# SW108_0713.net
KiCad netlist of a schematic drawn in Altium Designer
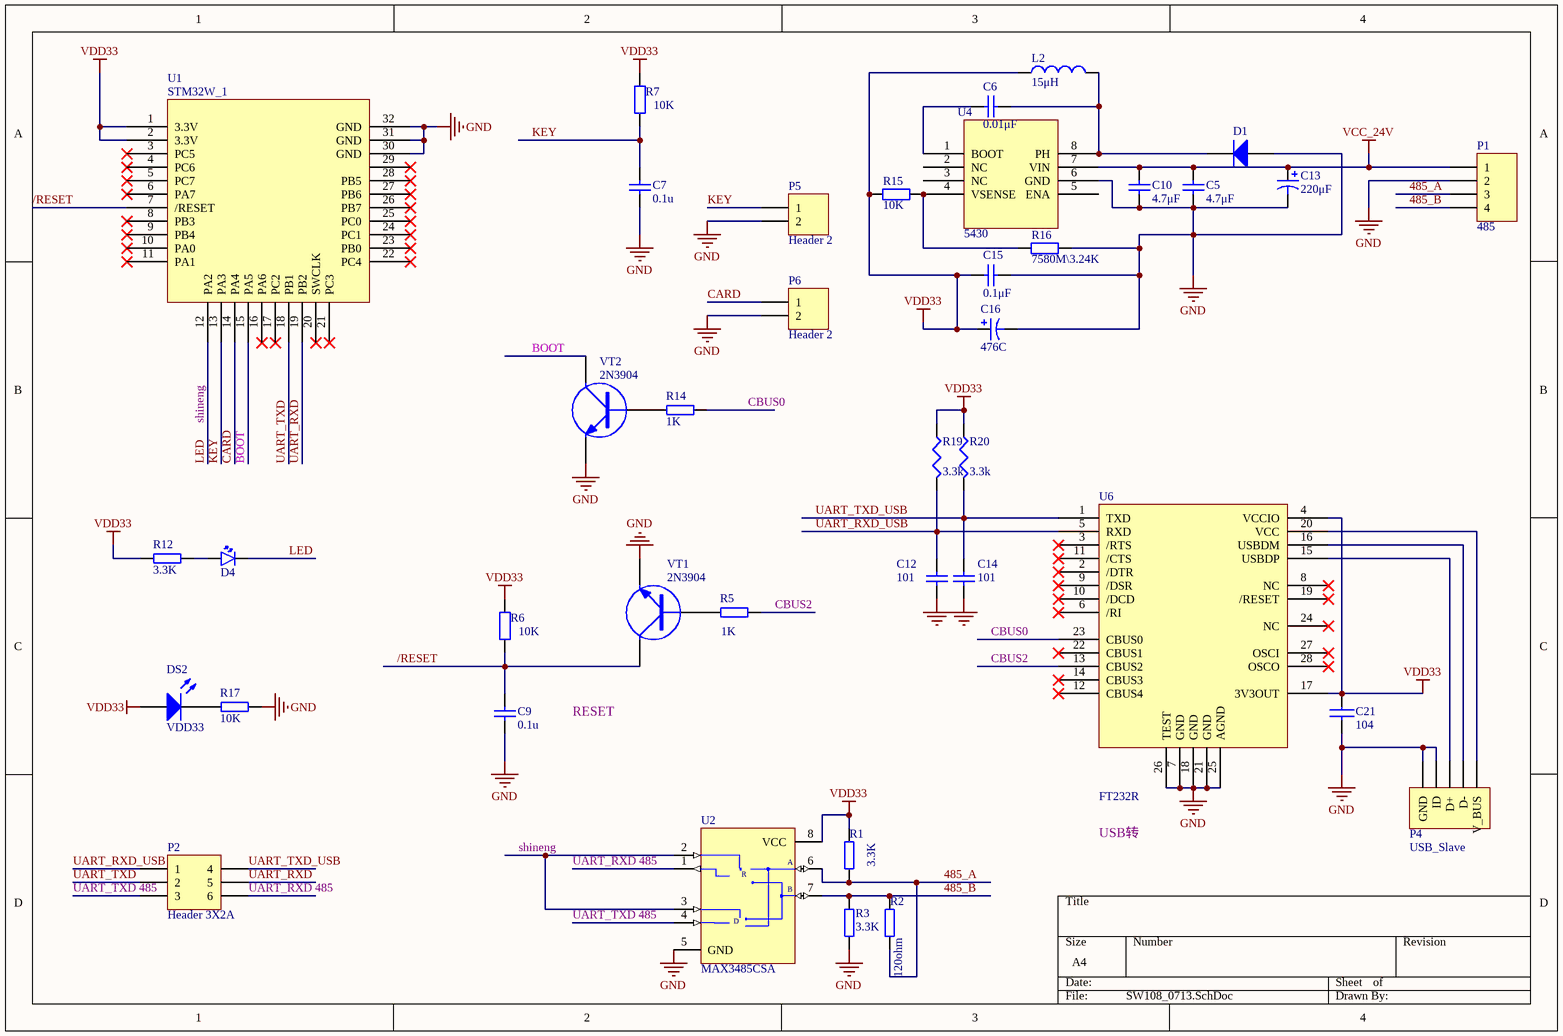
[diagram p0: SW108_0713.SchDoc]

(export (version "E")
  (design (tool "Eeschema 10.0.6"))
  (components
    (comp (ref "C5")
      (value "4.7μF")
      (footprint "C0603")
      (description "Capacitor")
      (fields (field (name "PUBLISHER") "Altium Limited"))
      (libsource (lib "Miscellaneous Devices") (part "Cap"))
    )
    (comp (ref "C6")
      (value "0.01μF")
      (footprint "C0603")
      (description "Capacitor")
      (fields (field (name "PUBLISHER") "Altium Limited"))
      (libsource (lib "Miscellaneous Devices") (part "Cap"))
    )
    (comp (ref "C7")
      (value "0.1u")
      (footprint "C0603")
      (description "Capacitor")
      (fields (field (name "PUBLISHER") "Altium Limited"))
      (libsource (lib "Miscellaneous Devices") (part "Cap"))
    )
    (comp (ref "C9")
      (value "0.1u")
      (footprint "C0603")
      (description "Capacitor")
      (fields (field (name "PUBLISHER") "Altium Limited"))
      (libsource (lib "Miscellaneous Devices") (part "Cap"))
    )
    (comp (ref "C10")
      (value "4.7μF")
      (footprint "C0603")
      (description "Capacitor")
      (fields (field (name "PUBLISHER") "Altium Limited"))
      (libsource (lib "Miscellaneous Devices") (part "Cap"))
    )
    (comp (ref "C12")
      (value "101")
      (footprint "C0603")
      (description "Capacitor")
      (fields (field (name "PUBLISHER") "Altium Limited"))
      (libsource (lib "Miscellaneous Devices") (part "Cap"))
    )
    (comp (ref "C13")
      (value "220μF")
      (footprint "CZ3.0/6.5")
      (description "Polarized Capacitor (Radial)")
      (fields (field (name "PUBLISHER") "Altium Limited"))
      (libsource (lib "Miscellaneous Devices") (part "Cap Pol1"))
    )
    (comp (ref "C14")
      (value "101")
      (footprint "C0603")
      (description "Capacitor")
      (fields (field (name "PUBLISHER") "Altium Limited"))
      (libsource (lib "Miscellaneous Devices") (part "Cap"))
    )
    (comp (ref "C15")
      (value "0.1μF")
      (footprint "C0603")
      (description "Capacitor")
      (fields (field (name "PUBLISHER") "Altium Limited"))
      (libsource (lib "Miscellaneous Devices") (part "Cap"))
    )
    (comp (ref "C16")
      (value "476C")
      (footprint "7343")
      (description "Polarized Capacitor (Radial)")
      (fields (field (name "PUBLISHER") "Altium Limited"))
      (libsource (lib "Miscellaneous Devices") (part "Cap Pol1"))
    )
    (comp (ref "C21") (value "104") (footprint "C0603") (description "C") (libsource (lib "Haze") (part "C")))
    (comp (ref "D1")
      (value "Diode 1N5408")
      (footprint "UF3B")
      (description "3 Amp Medium Power Silicon Rectifier Diode")
      (fields (field (name "PUBLISHER") "Altium Limited"))
      (libsource (lib "Miscellaneous Devices") (part "Diode 1N5408"))
    )
    (comp (ref "D4") (value "green LED") (footprint "LED") (libsource (lib "Haze") (part "LED")))
    (comp (ref "DS2")
      (value "VDD33")
      (footprint "LED")
      (description "Typical BLUE SiC LED")
      (fields (field (name "PUBLISHER") "Altium Limited"))
      (libsource (lib "Miscellaneous Devices") (part "LED3"))
    )
    (comp (ref "L2")
      (value "15μH")
      (footprint "L2")
      (description "Inductor")
      (fields (field (name "PUBLISHER") "Altium Limited"))
      (libsource (lib "Miscellaneous Devices") (part "Inductor"))
    )
    (comp (ref "P1")
      (value "485")
      (footprint "4kongzhen")
      (description "Header, 4-Pin")
      (fields (field (name "PUBLISHER") "Altium Limited"))
      (libsource (lib "Miscellaneous Connectors") (part "Header 4"))
    )
    (comp (ref "P2")
      (value "Header 3X2A")
      (footprint "HDR2X3_CEN")
      (description "Header, 3-Pin, Dual row")
      (fields (field (name "PUBLISHER") "Altium Limited"))
      (libsource (lib "Miscellaneous Connectors") (part "Header 3X2A"))
    )
    (comp (ref "P4")
      (value "USB_Slave")
      (footprint "USBfoot")
      (description "Header, 5-Pin")
      (fields (field (name "PUBLISHER") "Altium Limited"))
      (libsource (lib "Miscellaneous Connectors") (part "Header 5"))
    )
    (comp (ref "P5")
      (value "Header 2")
      (footprint "HDR1X2")
      (description "Header, 2-Pin")
      (fields (field (name "PUBLISHER") "Altium Limited"))
      (libsource (lib "Miscellaneous Connectors") (part "Header 2"))
    )
    (comp (ref "P6")
      (value "Header 2")
      (footprint "HDR1X2")
      (description "Header, 2-Pin")
      (fields (field (name "PUBLISHER") "Altium Limited"))
      (libsource (lib "Miscellaneous Connectors") (part "Header 2"))
    )
    (comp (ref "R1")
      (value "3.3K")
      (footprint "R0603")
      (description "R")
      (libsource (lib "Haze") (part "RES"))
    )
    (comp (ref "R2")
      (value "120ohm")
      (footprint "R0603")
      (description "R")
      (libsource (lib "Haze") (part "RES"))
    )
    (comp (ref "R3")
      (value "3.3K")
      (footprint "R0603")
      (description "R")
      (libsource (lib "Haze") (part "RES"))
    )
    (comp (ref "R5") (value "1K") (footprint "R0603") (description "R") (libsource (lib "Haze") (part "RES")))
    (comp (ref "R6")
      (value "10K")
      (footprint "R0603")
      (description "Resistor")
      (fields (field (name "Comment") "Res2") (field (name "PUBLISHER") "Altium Limited"))
      (libsource (lib "") (part "Res2_1"))
    )
    (comp (ref "R7")
      (value "10K")
      (footprint "R0603")
      (description "Resistor")
      (fields (field (name "Comment") "Res2") (field (name "PUBLISHER") "Altium Limited"))
      (libsource (lib "") (part "Res2_1"))
    )
    (comp (ref "R12")
      (value "3.3K")
      (footprint "R0603")
      (description "R")
      (libsource (lib "Haze") (part "RES"))
    )
    (comp (ref "R14")
      (value "1K")
      (footprint "R0603")
      (description "R")
      (libsource (lib "Haze") (part "RES"))
    )
    (comp (ref "R15")
      (value "10K")
      (footprint "R0603")
      (description "Resistor")
      (fields (field (name "PUBLISHER") "Altium Limited"))
      (libsource (lib "Miscellaneous Devices") (part "Res2"))
    )
    (comp (ref "R16")
      (value "7580~{M}3.24K")
      (footprint "R0603")
      (description "Resistor")
      (fields (field (name "PUBLISHER") "Altium Limited"))
      (libsource (lib "Miscellaneous Devices") (part "Res2"))
    )
    (comp (ref "R17")
      (value "10K")
      (footprint "R0603")
      (description "R")
      (libsource (lib "Haze") (part "RES"))
    )
    (comp (ref "R19")
      (value "3.3k")
      (footprint "R0603")
      (description "Resistor")
      (fields (field (name "PUBLISHER") "Altium Limited"))
      (libsource (lib "Miscellaneous Devices") (part "Res3"))
    )
    (comp (ref "R20")
      (value "3.3k")
      (footprint "R0603")
      (description "Resistor")
      (fields (field (name "PUBLISHER") "Altium Limited"))
      (libsource (lib "Miscellaneous Devices") (part "Res3"))
    )
    (comp (ref "U1")
      (value "STM32W_1")
      (footprint "STM32W108-3")
      (libsource (lib "STM32W108-3") (part "STM32W108-3"))
    )
    (comp (ref "U2")
      (value "MAX3485CSA")
      (footprint "SO-8")
      (description "Low-Power, Slew-Rate-Limited RS-485/RS-422 Transceiver")
      (fields (field (name "PUBLISHER") "Altium Limited"))
      (libsource (lib "Maxim Communication Transceiver") (part "MAX485CSA"))
    )
    (comp (ref "U4") (value "5430") (footprint "SO-8") (libsource (lib "Haze") (part "5430")))
    (comp (ref "U6") (value "FT232R") (footprint "SSOP-28") (libsource (lib "Haze") (part "FT232R")))
    (comp (ref "VT1")
      (value "2N3904")
      (footprint "SOT23-3")
      (description "NPN Transistor")
      (libsource (lib "Haze") (part "NPN"))
    )
    (comp (ref "VT2")
      (value "2N3904")
      (footprint "SOT23-3")
      (description "NPN Transistor")
      (libsource (lib "Haze") (part "NPN"))
    )
  )
  (nets
    (net (code "1") (name "/485_A") (class "Default")
      (node (ref "P1") (pin "3") (pinfunction "3_3") (pintype "passive"))
      (node (ref "R1") (pin "1") (pinfunction "1_1") (pintype "passive"))
      (node (ref "R2") (pin "2") (pinfunction "2_2") (pintype "passive"))
      (node (ref "U2") (pin "6") (pinfunction "A_6") (pintype "bidirectional"))
    )
    (net (code "2") (name "/485_B") (class "Default")
      (node (ref "P1") (pin "4") (pinfunction "4_4") (pintype "passive"))
      (node (ref "R2") (pin "1") (pinfunction "1_1") (pintype "passive"))
      (node (ref "R3") (pin "2") (pinfunction "2_2") (pintype "passive"))
      (node (ref "U2") (pin "7") (pinfunction "B_7") (pintype "bidirectional"))
    )
    (net (code "3") (name "/BOOT") (class "Default")
      (node (ref "U1") (pin "15") (pinfunction "PA5_15") (pintype "passive"))
      (node (ref "VT2") (pin "3") (pinfunction "C_3") (pintype "passive"))
    )
    (net (code "4") (name "/CARD") (class "Default")
      (node (ref "P6") (pin "1") (pinfunction "1_1") (pintype "passive"))
      (node (ref "U1") (pin "14") (pinfunction "PA4_14") (pintype "passive"))
    )
    (net (code "5") (name "/CBUS0") (class "Default")
      (node (ref "R14") (pin "2") (pinfunction "2_2") (pintype "passive"))
      (node (ref "U6") (pin "23") (pinfunction "CBUS0_23") (pintype "passive"))
    )
    (net (code "6") (name "/CBUS2") (class "Default")
      (node (ref "R5") (pin "2") (pinfunction "2_2") (pintype "passive"))
      (node (ref "U6") (pin "13") (pinfunction "CBUS2_13") (pintype "passive"))
    )
    (net (code "7") (name "/KEY") (class "Default")
      (node (ref "C7") (pin "2") (pinfunction "2_2") (pintype "passive"))
      (node (ref "P5") (pin "1") (pinfunction "1_1") (pintype "passive"))
      (node (ref "R7") (pin "1") (pinfunction "1_1") (pintype "passive"))
      (node (ref "U1") (pin "13") (pinfunction "PA3_13") (pintype "passive"))
    )
    (net (code "8") (name "/LED") (class "Default")
      (node (ref "D4") (pin "2") (pinfunction "K_2") (pintype "passive"))
      (node (ref "U1") (pin "12") (pinfunction "PA2_12") (pintype "passive"))
      (node (ref "U2") (pin "2") (pinfunction "~{RE}_2") (pintype "input"))
      (node (ref "U2") (pin "3") (pinfunction "DE_3") (pintype "input"))
    )
    (net (code "9") (name "/UART_RXD") (class "Default")
      (node (ref "P2") (pin "5") (pinfunction "5_5") (pintype "passive"))
      (node (ref "U1") (pin "19") (pinfunction "PB2_19") (pintype "passive"))
    )
    (net (code "10") (name "/UART_RXD 485") (class "Default")
      (node (ref "P2") (pin "6") (pinfunction "6_6") (pintype "passive"))
      (node (ref "U2") (pin "1") (pinfunction "RO_1") (pintype "output"))
    )
    (net (code "11") (name "/UART_RXD_USB") (class "Default")
      (node (ref "C12") (pin "2") (pinfunction "2_2") (pintype "passive"))
      (node (ref "P2") (pin "1") (pinfunction "1_1") (pintype "passive"))
      (node (ref "R19") (pin "2") (pinfunction "2_2") (pintype "passive"))
      (node (ref "U6") (pin "5") (pinfunction "RXD_5") (pintype "passive"))
    )
    (net (code "12") (name "/UART_TXD") (class "Default")
      (node (ref "P2") (pin "2") (pinfunction "2_2") (pintype "passive"))
      (node (ref "U1") (pin "18") (pinfunction "PB1_18") (pintype "passive"))
    )
    (net (code "13") (name "/UART_TXD 485") (class "Default")
      (node (ref "P2") (pin "3") (pinfunction "3_3") (pintype "passive"))
      (node (ref "U2") (pin "4") (pinfunction "DI_4") (pintype "input"))
    )
    (net (code "14") (name "/UART_TXD_USB") (class "Default")
      (node (ref "C14") (pin "2") (pinfunction "2_2") (pintype "passive"))
      (node (ref "P2") (pin "4") (pinfunction "4_4") (pintype "passive"))
      (node (ref "R20") (pin "2") (pinfunction "2_2") (pintype "passive"))
      (node (ref "U6") (pin "1") (pinfunction "TXD_1") (pintype "passive"))
    )
    (net (code "15") (name "/{slash}RESET") (class "Default")
      (node (ref "C9") (pin "2") (pinfunction "2_2") (pintype "passive"))
      (node (ref "R6") (pin "1") (pinfunction "1_1") (pintype "passive"))
      (node (ref "U1") (pin "7") (pinfunction "/RESET_7") (pintype "passive"))
      (node (ref "VT1") (pin "3") (pinfunction "C_3") (pintype "passive"))
    )
    (net (code "16") (name "GND") (class "Default")
      (node (ref "C10") (pin "1") (pinfunction "1_1") (pintype "passive"))
      (node (ref "C12") (pin "1") (pinfunction "1_1") (pintype "passive"))
      (node (ref "C13") (pin "2") (pinfunction "2_2") (pintype "passive"))
      (node (ref "C14") (pin "1") (pinfunction "1_1") (pintype "passive"))
      (node (ref "C15") (pin "2") (pinfunction "2_2") (pintype "passive"))
      (node (ref "C16") (pin "2") (pinfunction "2_2") (pintype "passive"))
      (node (ref "C21") (pin "2") (pinfunction "2_2") (pintype "passive"))
      (node (ref "C5") (pin "1") (pinfunction "1_1") (pintype "passive"))
      (node (ref "C7") (pin "1") (pinfunction "1_1") (pintype "passive"))
      (node (ref "C9") (pin "1") (pinfunction "1_1") (pintype "passive"))
      (node (ref "D1") (pin "1") (pinfunction "A_1") (pintype "passive"))
      (node (ref "P1") (pin "2") (pinfunction "2_2") (pintype "passive"))
      (node (ref "P4") (pin "4") (pinfunction "ID_4") (pintype "passive"))
      (node (ref "P4") (pin "5") (pinfunction "GND_5") (pintype "passive"))
      (node (ref "P5") (pin "2") (pinfunction "2_2") (pintype "passive"))
      (node (ref "P6") (pin "2") (pinfunction "2_2") (pintype "passive"))
      (node (ref "R16") (pin "2") (pinfunction "2_2") (pintype "passive"))
      (node (ref "R17") (pin "1") (pinfunction "1_1") (pintype "passive"))
      (node (ref "R3") (pin "1") (pinfunction "1_1") (pintype "passive"))
      (node (ref "U1") (pin "30") (pinfunction "GND_30") (pintype "passive"))
      (node (ref "U1") (pin "31") (pinfunction "GND_31") (pintype "passive"))
      (node (ref "U1") (pin "32") (pinfunction "GND_32") (pintype "passive"))
      (node (ref "U2") (pin "5") (pinfunction "GND_5") (pintype "power_in"))
      (node (ref "U4") (pin "6") (pinfunction "GND_6") (pintype "passive"))
      (node (ref "U6") (pin "18") (pinfunction "GND_18") (pintype "passive"))
      (node (ref "U6") (pin "21") (pinfunction "GND_21") (pintype "passive"))
      (node (ref "U6") (pin "25") (pinfunction "AGND_25") (pintype "passive"))
      (node (ref "U6") (pin "26") (pinfunction "TEST_26") (pintype "passive"))
      (node (ref "U6") (pin "7") (pinfunction "GND_7") (pintype "passive"))
      (node (ref "VT1") (pin "2") (pinfunction "E_2") (pintype "passive"))
      (node (ref "VT2") (pin "2") (pinfunction "E_2") (pintype "passive"))
    )
    (net (code "17") (name "Net-(D1-K)") (class "Default")
      (node (ref "C6") (pin "2") (pinfunction "2_2") (pintype "passive"))
      (node (ref "D1") (pin "2") (pinfunction "K_2") (pintype "passive"))
      (node (ref "L2") (pin "2") (pinfunction "2_2") (pintype "passive"))
      (node (ref "U4") (pin "8") (pinfunction "PH_8") (pintype "passive"))
    )
    (net (code "18") (name "Net-(D4-A)") (class "Default")
      (node (ref "D4") (pin "1") (pinfunction "A_1") (pintype "passive"))
      (node (ref "R12") (pin "2") (pinfunction "2_2") (pintype "passive"))
    )
    (net (code "19") (name "Net-(DS2-K)") (class "Default")
      (node (ref "DS2") (pin "2") (pinfunction "K_2") (pintype "passive"))
      (node (ref "R17") (pin "2") (pinfunction "2_2") (pintype "passive"))
    )
    (net (code "20") (name "Net-(P4-D+)") (class "Default")
      (node (ref "P4") (pin "3") (pinfunction "D+_3") (pintype "passive"))
      (node (ref "U6") (pin "15") (pinfunction "USBDP_15") (pintype "passive"))
    )
    (net (code "21") (name "Net-(P4-D-)") (class "Default")
      (node (ref "P4") (pin "2") (pinfunction "D-_2") (pintype "passive"))
      (node (ref "U6") (pin "16") (pinfunction "USBDM_16") (pintype "passive"))
    )
    (net (code "22") (name "Net-(P4-V_BUS)") (class "Default")
      (node (ref "P4") (pin "1") (pinfunction "V_BUS_1") (pintype "passive"))
      (node (ref "U6") (pin "20") (pinfunction "VCC_20") (pintype "passive"))
    )
    (net (code "23") (name "Net-(U4-BOOT)") (class "Default")
      (node (ref "C6") (pin "1") (pinfunction "1_1") (pintype "passive"))
      (node (ref "U4") (pin "1") (pinfunction "BOOT_1") (pintype "passive"))
    )
    (net (code "24") (name "Net-(U4-VSENSE)") (class "Default")
      (node (ref "R15") (pin "2") (pinfunction "2_2") (pintype "passive"))
      (node (ref "R16") (pin "1") (pinfunction "1_1") (pintype "passive"))
      (node (ref "U4") (pin "4") (pinfunction "VSENSE_4") (pintype "passive"))
    )
    (net (code "25") (name "Net-(VT1-B)") (class "Default")
      (node (ref "R5") (pin "1") (pinfunction "1_1") (pintype "passive"))
      (node (ref "VT1") (pin "1") (pinfunction "B_1") (pintype "passive"))
    )
    (net (code "26") (name "Net-(VT2-B)") (class "Default")
      (node (ref "R14") (pin "1") (pinfunction "1_1") (pintype "passive"))
      (node (ref "VT2") (pin "1") (pinfunction "B_1") (pintype "passive"))
    )
    (net (code "27") (name "VCC_24V") (class "Default")
      (node (ref "C10") (pin "2") (pinfunction "2_2") (pintype "passive"))
      (node (ref "C13") (pin "1") (pinfunction "1_1") (pintype "passive"))
      (node (ref "C5") (pin "2") (pinfunction "2_2") (pintype "passive"))
      (node (ref "P1") (pin "1") (pinfunction "1_1") (pintype "passive"))
      (node (ref "U4") (pin "7") (pinfunction "VIN_7") (pintype "passive"))
    )
    (net (code "28") (name "VDD33") (class "Default")
      (node (ref "C15") (pin "1") (pinfunction "1_1") (pintype "passive"))
      (node (ref "C16") (pin "1") (pinfunction "1_1") (pintype "passive"))
      (node (ref "C21") (pin "1") (pinfunction "1_1") (pintype "passive"))
      (node (ref "DS2") (pin "1") (pinfunction "A_1") (pintype "passive"))
      (node (ref "L2") (pin "1") (pinfunction "1_1") (pintype "passive"))
      (node (ref "R1") (pin "2") (pinfunction "2_2") (pintype "passive"))
      (node (ref "R12") (pin "1") (pinfunction "1_1") (pintype "passive"))
      (node (ref "R15") (pin "1") (pinfunction "1_1") (pintype "passive"))
      (node (ref "R19") (pin "1") (pinfunction "1_1") (pintype "passive"))
      (node (ref "R20") (pin "1") (pinfunction "1_1") (pintype "passive"))
      (node (ref "R6") (pin "2") (pinfunction "2_2") (pintype "passive"))
      (node (ref "R7") (pin "2") (pinfunction "2_2") (pintype "passive"))
      (node (ref "U1") (pin "1") (pinfunction "3.3V_1") (pintype "passive"))
      (node (ref "U1") (pin "2") (pinfunction "3.3V_2") (pintype "passive"))
      (node (ref "U2") (pin "8") (pinfunction "VCC_8") (pintype "power_in"))
      (node (ref "U6") (pin "17") (pinfunction "3V3OUT_17") (pintype "passive"))
      (node (ref "U6") (pin "4") (pinfunction "VCCIO_4") (pintype "passive"))
    )
    (net (code "29") (name "unconnected-(U1-PA0-Pad10)") (class "Default")
      (node (ref "U1") (pin "10") (pinfunction "PA0_10") (pintype "passive+no_connect"))
    )
    (net (code "30") (name "unconnected-(U1-PA1-Pad11)") (class "Default")
      (node (ref "U1") (pin "11") (pinfunction "PA1_11") (pintype "passive+no_connect"))
    )
    (net (code "31") (name "unconnected-(U1-PA6-Pad16)") (class "Default")
      (node (ref "U1") (pin "16") (pinfunction "PA6_16") (pintype "passive+no_connect"))
    )
    (net (code "32") (name "unconnected-(U1-PA7-Pad6)") (class "Default")
      (node (ref "U1") (pin "6") (pinfunction "PA7_6") (pintype "passive+no_connect"))
    )
    (net (code "33") (name "unconnected-(U1-PB0-Pad23)") (class "Default")
      (node (ref "U1") (pin "23") (pinfunction "PB0_23") (pintype "passive+no_connect"))
    )
    (net (code "34") (name "unconnected-(U1-PB3-Pad8)") (class "Default")
      (node (ref "U1") (pin "8") (pinfunction "PB3_8") (pintype "passive+no_connect"))
    )
    (net (code "35") (name "unconnected-(U1-PB4-Pad9)") (class "Default")
      (node (ref "U1") (pin "9") (pinfunction "PB4_9") (pintype "passive+no_connect"))
    )
    (net (code "36") (name "unconnected-(U1-PB5-Pad28)") (class "Default")
      (node (ref "U1") (pin "28") (pinfunction "PB5_28") (pintype "passive+no_connect"))
    )
    (net (code "37") (name "unconnected-(U1-PB6-Pad27)") (class "Default")
      (node (ref "U1") (pin "27") (pinfunction "PB6_27") (pintype "passive+no_connect"))
    )
    (net (code "38") (name "unconnected-(U1-PB7-Pad26)") (class "Default")
      (node (ref "U1") (pin "26") (pinfunction "PB7_26") (pintype "passive+no_connect"))
    )
    (net (code "39") (name "unconnected-(U1-PC0-Pad25)") (class "Default")
      (node (ref "U1") (pin "25") (pinfunction "PC0_25") (pintype "passive+no_connect"))
    )
    (net (code "40") (name "unconnected-(U1-PC1-Pad24)") (class "Default")
      (node (ref "U1") (pin "24") (pinfunction "PC1_24") (pintype "passive+no_connect"))
    )
    (net (code "41") (name "unconnected-(U1-PC2-Pad17)") (class "Default")
      (node (ref "U1") (pin "17") (pinfunction "PC2_17") (pintype "passive+no_connect"))
    )
    (net (code "42") (name "unconnected-(U1-PC3-Pad21)") (class "Default")
      (node (ref "U1") (pin "21") (pinfunction "PC3_21") (pintype "passive+no_connect"))
    )
    (net (code "43") (name "unconnected-(U1-PC4-Pad22)") (class "Default")
      (node (ref "U1") (pin "22") (pinfunction "PC4_22") (pintype "passive+no_connect"))
    )
    (net (code "44") (name "unconnected-(U1-PC5-Pad3)") (class "Default")
      (node (ref "U1") (pin "3") (pinfunction "PC5_3") (pintype "passive+no_connect"))
    )
    (net (code "45") (name "unconnected-(U1-PC6-Pad4)") (class "Default")
      (node (ref "U1") (pin "4") (pinfunction "PC6_4") (pintype "passive+no_connect"))
    )
    (net (code "46") (name "unconnected-(U1-PC7-Pad5)") (class "Default")
      (node (ref "U1") (pin "5") (pinfunction "PC7_5") (pintype "passive+no_connect"))
    )
    (net (code "47") (name "unconnected-(U1-Pad29)") (class "Default")
      (node (ref "U1") (pin "29") (pintype "passive+no_connect"))
    )
    (net (code "48") (name "unconnected-(U1-SWCLK-Pad20)") (class "Default")
      (node (ref "U1") (pin "20") (pinfunction "SWCLK_20") (pintype "passive+no_connect"))
    )
    (net (code "49") (name "unconnected-(U4-ENA-Pad5)") (class "Default")
      (node (ref "U4") (pin "5") (pinfunction "ENA_5") (pintype "passive"))
    )
    (net (code "50") (name "unconnected-(U4-NC-Pad2)") (class "Default")
      (node (ref "U4") (pin "2") (pinfunction "NC_2") (pintype "passive"))
    )
    (net (code "51") (name "unconnected-(U4-NC-Pad3)") (class "Default")
      (node (ref "U4") (pin "3") (pinfunction "NC_3") (pintype "passive"))
    )
    (net (code "52") (name "unconnected-(U6-CBUS1-Pad22)") (class "Default")
      (node (ref "U6") (pin "22") (pinfunction "CBUS1_22") (pintype "passive+no_connect"))
    )
    (net (code "53") (name "unconnected-(U6-CBUS3-Pad14)") (class "Default")
      (node (ref "U6") (pin "14") (pinfunction "CBUS3_14") (pintype "passive+no_connect"))
    )
    (net (code "54") (name "unconnected-(U6-CBUS4-Pad12)") (class "Default")
      (node (ref "U6") (pin "12") (pinfunction "CBUS4_12") (pintype "passive+no_connect"))
    )
    (net (code "55") (name "unconnected-(U6-NC-Pad8)") (class "Default")
      (node (ref "U6") (pin "8") (pinfunction "NC_8") (pintype "passive+no_connect"))
    )
    (net (code "56") (name "unconnected-(U6-NC-Pad24)") (class "Default")
      (node (ref "U6") (pin "24") (pinfunction "NC_24") (pintype "passive+no_connect"))
    )
    (net (code "57") (name "unconnected-(U6-OSCI-Pad27)") (class "Default")
      (node (ref "U6") (pin "27") (pinfunction "OSCI_27") (pintype "passive+no_connect"))
    )
    (net (code "58") (name "unconnected-(U6-OSCO-Pad28)") (class "Default")
      (node (ref "U6") (pin "28") (pinfunction "OSCO_28") (pintype "passive+no_connect"))
    )
    (net (code "59") (name "unconnected-(U6-{slash}CTS-Pad11)") (class "Default")
      (node (ref "U6") (pin "11") (pinfunction "/CTS_11") (pintype "passive+no_connect"))
    )
    (net (code "60") (name "unconnected-(U6-{slash}DCD-Pad10)") (class "Default")
      (node (ref "U6") (pin "10") (pinfunction "/DCD_10") (pintype "passive+no_connect"))
    )
    (net (code "61") (name "unconnected-(U6-{slash}DSR-Pad9)") (class "Default")
      (node (ref "U6") (pin "9") (pinfunction "/DSR_9") (pintype "passive+no_connect"))
    )
    (net (code "62") (name "unconnected-(U6-{slash}DTR-Pad2)") (class "Default")
      (node (ref "U6") (pin "2") (pinfunction "/DTR_2") (pintype "passive+no_connect"))
    )
    (net (code "63") (name "unconnected-(U6-{slash}RESET-Pad19)") (class "Default")
      (node (ref "U6") (pin "19") (pinfunction "/RESET_19") (pintype "passive+no_connect"))
    )
    (net (code "64") (name "unconnected-(U6-{slash}RI-Pad6)") (class "Default")
      (node (ref "U6") (pin "6") (pinfunction "/RI_6") (pintype "passive+no_connect"))
    )
    (net (code "65") (name "unconnected-(U6-{slash}RTS-Pad3)") (class "Default")
      (node (ref "U6") (pin "3") (pinfunction "/RTS_3") (pintype "passive+no_connect"))
    )
  )
)
